# Microcontroller.net
KiCad netlist of a schematic drawn in Altium Designer
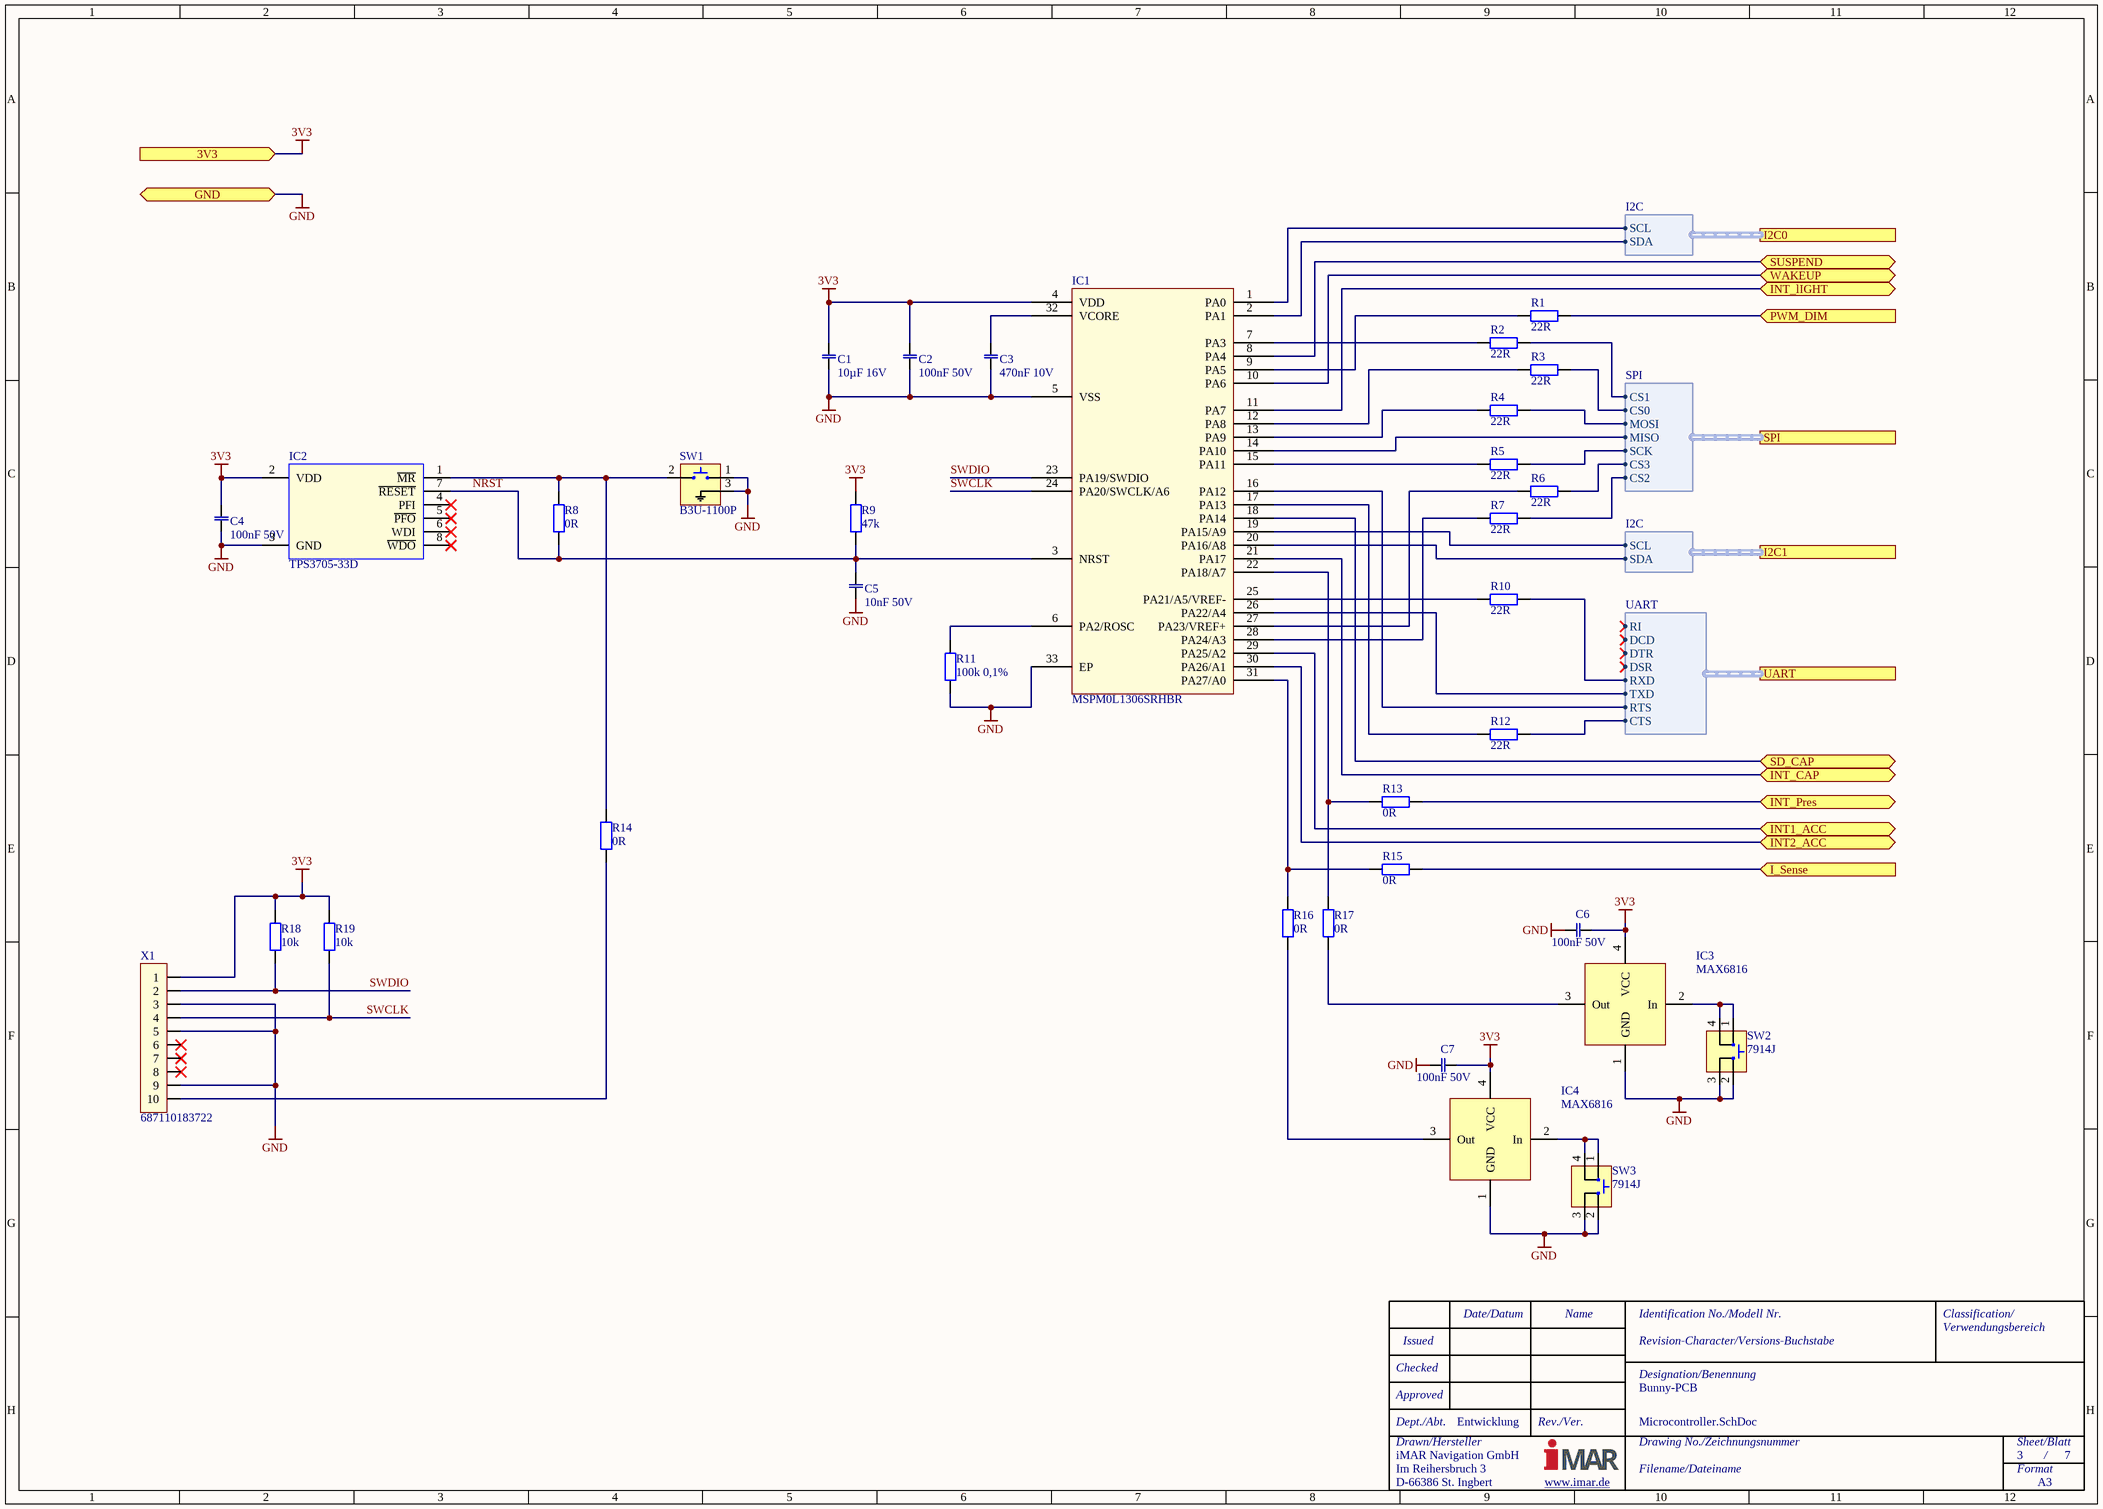
[diagram p0: Microcontroller.SchDoc]

(export (version "E")
  (design (tool "Eeschema 10.0.6"))
  (components
    (comp (ref "C1")
      (value "10µF 16V")
      (footprint "CAPC1608L")
      (description "10µF  16V  Ceramic  0603  10%  X5R")
      (fields (field (name "TOLERANCE") "10%") (field (name "MANUFACTURER") "unspecified"))
      (libsource (lib "iMAR Workspace") (part "Kondensator"))
    )
    (comp (ref "C2")
      (value "100nF 50V")
      (footprint "CAPC1005N")
      (description "100nF  50V  Ceramic  0402  10%  X7R")
      (fields (field (name "VOLTAGE") "50V") (field (name "MANUFACTURER") "unspecified"))
      (libsource (lib "iMAR Workspace") (part "Kondensator"))
    )
    (comp (ref "C3")
      (value "470nF 10V")
      (footprint "CAPC1005N")
      (description "470nF  10V  Ceramic  0402  10%  X5R")
      (fields (field (name "MANUFACTURER") "unspecified") (field (name "VOLTAGE") "10V"))
      (libsource (lib "iMAR Workspace") (part "Kondensator"))
    )
    (comp (ref "C4")
      (value "100nF 50V")
      (footprint "CAPC1005N")
      (description "100nF  50V  Ceramic  0402  10%  X7R")
      (fields (field (name "VOLTAGE") "50V") (field (name "MANUFACTURER") "unspecified"))
      (libsource (lib "iMAR Workspace") (part "Kondensator"))
    )
    (comp (ref "C5")
      (value "10nF 50V")
      (footprint "CAPC1005N")
      (description "10nF  50V  Ceramic  0402  10%  X7R")
      (fields (field (name "MANUFACTURER") "unspecified") (field (name "VOLTAGE") "50V"))
      (libsource (lib "iMAR Workspace") (part "Kondensator"))
    )
    (comp (ref "C6")
      (value "100nF 50V")
      (footprint "CAPC1005N")
      (description "100nF  50V  Ceramic  0402  10%  X7R")
      (fields (field (name "VOLTAGE") "50V") (field (name "MANUFACTURER") "unspecified"))
      (libsource (lib "iMAR Workspace") (part "Kondensator"))
    )
    (comp (ref "C7")
      (value "100nF 50V")
      (footprint "CAPC1005N")
      (description "100nF  50V  Ceramic  0402  10%  X7R")
      (fields (field (name "VOLTAGE") "50V") (field (name "MANUFACTURER") "unspecified"))
      (libsource (lib "iMAR Workspace") (part "Kondensator"))
    )
    (comp (ref "IC1")
      (value "MSPM0L1306SRHBR")
      (footprint "QFN50P500X500X80_HS-33N")
      (description "ARM Microcontrollers - MCU 32-MHz Arm Cortex - M0+ MCU with 64-KB")
      (fields (field (name "MANUFACTURER") "TEXAS INSTRUMENTS"))
      (libsource (lib "iMAR Workspace") (part "MSPM0L1306RHB"))
    )
    (comp (ref "IC2")
      (value "TPS3705-33D")
      (footprint "SOIC127P600X175-8N")
      (description "Überwachungsschaltung, Active-Low, Push-Pull-Reset, 2 Überwachungsschaltungen, 2V-6Vin, SOIC-8")
      (fields (field (name "MANUFACTURER") "TEXAS INSTRUMENTS"))
      (libsource (lib "iMAR Workspace") (part "TPS3705-33D"))
    )
    (comp (ref "IC3")
      (value "MAX6816")
      (footprint "SOT190P237X120-4N")
      (description "CMOS Switch Debouncers ±15kV ESD-Protected, Single/Dual/Octal,")
      (fields (field (name "MANUFACTURER") "MAXIM INTEGRATED"))
      (libsource (lib "iMAR Workspace") (part "MAX6816"))
    )
    (comp (ref "IC4")
      (value "MAX6816")
      (footprint "SOT190P237X120-4N")
      (description "CMOS Switch Debouncers ±15kV ESD-Protected, Single/Dual/Octal,")
      (fields (field (name "MANUFACTURER") "MAXIM INTEGRATED"))
      (libsource (lib "iMAR Workspace") (part "MAX6816"))
    )
    (comp (ref "R1")
      (value "22R")
      (footprint "RESC1005L")
      (description "22R  0402  62mW  1%  100ppm  50V")
      (fields (field (name "MANUFACTURER") "unspecified") (field (name "POWER") "62mW"))
      (libsource (lib "") (part "Widerstand_1"))
    )
    (comp (ref "R2")
      (value "22R")
      (footprint "RESC1005L")
      (description "22R  0402  62mW  1%  100ppm  50V")
      (fields (field (name "MANUFACTURER") "unspecified") (field (name "POWER") "62mW"))
      (libsource (lib "") (part "Widerstand_1"))
    )
    (comp (ref "R3")
      (value "22R")
      (footprint "RESC1005L")
      (description "22R  0402  62mW  1%  100ppm  50V")
      (fields (field (name "MANUFACTURER") "unspecified") (field (name "POWER") "62mW"))
      (libsource (lib "") (part "Widerstand_1"))
    )
    (comp (ref "R4")
      (value "22R")
      (footprint "RESC1005L")
      (description "22R  0402  62mW  1%  100ppm  50V")
      (fields (field (name "MANUFACTURER") "unspecified") (field (name "POWER") "62mW"))
      (libsource (lib "") (part "Widerstand_1"))
    )
    (comp (ref "R5")
      (value "22R")
      (footprint "RESC1005L")
      (description "22R  0402  62mW  1%  100ppm  50V")
      (fields (field (name "MANUFACTURER") "unspecified") (field (name "POWER") "62mW"))
      (libsource (lib "") (part "Widerstand_1"))
    )
    (comp (ref "R6")
      (value "22R")
      (footprint "RESC1005L")
      (description "22R  0402  62mW  1%  100ppm  50V")
      (fields (field (name "MANUFACTURER") "unspecified") (field (name "POWER") "62mW"))
      (libsource (lib "") (part "Widerstand_1"))
    )
    (comp (ref "R7")
      (value "22R")
      (footprint "RESC1005L")
      (description "22R  0402  62mW  1%  100ppm  50V")
      (fields (field (name "MANUFACTURER") "unspecified") (field (name "POWER") "62mW"))
      (libsource (lib "") (part "Widerstand_1"))
    )
    (comp (ref "R8")
      (value "0R")
      (footprint "RESC1005L")
      (description "0R  0402  0mW  0%  0ppm  0V")
      (fields (field (name "VOLTAGE") "0V") (field (name "TOLERANCE") "0%"))
      (libsource (lib "iMAR Workspace") (part "Widerstand"))
    )
    (comp (ref "R9")
      (value "47k")
      (footprint "RESC1005L")
      (description "47k  0402  62mW  1%  100ppm  50V")
      (fields (field (name "MANUFACTURER") "unspecified") (field (name "POWER") "62mW"))
      (libsource (lib "iMAR Workspace") (part "Widerstand"))
    )
    (comp (ref "R10")
      (value "22R")
      (footprint "RESC1005L")
      (description "22R  0402  62mW  1%  100ppm  50V")
      (fields (field (name "MANUFACTURER") "unspecified") (field (name "POWER") "62mW"))
      (libsource (lib "") (part "Widerstand_1"))
    )
    (comp (ref "R11")
      (value "100k 0,1%")
      (footprint "RESC1005L")
      (description "100k  0402  62mW  0,1%  25ppm  50V")
      (fields (field (name "POWER") "62mW") (field (name "VOLTAGE") "50V"))
      (libsource (lib "iMAR Workspace") (part "Widerstand"))
    )
    (comp (ref "R12")
      (value "22R")
      (footprint "RESC1005L")
      (description "22R  0402  62mW  1%  100ppm  50V")
      (fields (field (name "MANUFACTURER") "unspecified") (field (name "POWER") "62mW"))
      (libsource (lib "") (part "Widerstand_1"))
    )
    (comp (ref "R13")
      (value "0R")
      (footprint "RESC1005L")
      (description "0R  0402  0mW  0%  0ppm  0V")
      (fields (field (name "VOLTAGE") "0V") (field (name "TOLERANCE") "0%"))
      (libsource (lib "") (part "Widerstand_2"))
    )
    (comp (ref "R14")
      (value "0R")
      (footprint "RESC1005L")
      (description "0R  0402  0mW  0%  0ppm  0V")
      (fields (field (name "VOLTAGE") "0V") (field (name "TOLERANCE") "0%"))
      (libsource (lib "iMAR Workspace") (part "Widerstand"))
    )
    (comp (ref "R15")
      (value "0R")
      (footprint "RESC1005L")
      (description "0R  0402  0mW  0%  0ppm  0V")
      (fields (field (name "VOLTAGE") "0V") (field (name "TOLERANCE") "0%"))
      (libsource (lib "") (part "Widerstand_2"))
    )
    (comp (ref "R16")
      (value "0R")
      (footprint "RESC1005L")
      (description "0R  0402  0mW  0%  0ppm  0V")
      (fields (field (name "VOLTAGE") "0V") (field (name "TOLERANCE") "0%"))
      (libsource (lib "iMAR Workspace") (part "Widerstand"))
    )
    (comp (ref "R17")
      (value "0R")
      (footprint "RESC1005L")
      (description "0R  0402  0mW  0%  0ppm  0V")
      (fields (field (name "VOLTAGE") "0V") (field (name "TOLERANCE") "0%"))
      (libsource (lib "iMAR Workspace") (part "Widerstand"))
    )
    (comp (ref "R18")
      (value "10k")
      (footprint "RESC1005L")
      (description "10k  0402  62mW  1%  100ppm  50V")
      (fields (field (name "MANUFACTURER") "unspecified") (field (name "POWER") "62mW"))
      (libsource (lib "iMAR Workspace") (part "Widerstand"))
    )
    (comp (ref "R19")
      (value "10k")
      (footprint "RESC1005L")
      (description "10k  0402  62mW  1%  100ppm  50V")
      (fields (field (name "MANUFACTURER") "unspecified") (field (name "POWER") "62mW"))
      (libsource (lib "iMAR Workspace") (part "Widerstand"))
    )
    (comp (ref "SW1")
      (value "B3U-1100P")
      (footprint "OMRON_B3U-1100P")
      (fields (field (name "MANUFACTURER") "OMRON"))
      (libsource (lib "iMAR Workspace") (part "Taster SPST NO-Schliesser 2 Pin mit Gehäuse-Pin"))
    )
    (comp (ref "SW2")
      (value "7914J")
      (footprint "BOURNS_7914J")
      (description "SMD Pushbutton Sealed")
      (fields (field (name "MANUFACTURER") "BOURNS"))
      (libsource (lib "iMAR Workspace") (part "Taster SPST NO-Schliesser 4 Pins"))
    )
    (comp (ref "SW3")
      (value "7914J")
      (footprint "BOURNS_7914J")
      (description "SMD Pushbutton Sealed")
      (fields (field (name "MANUFACTURER") "BOURNS"))
      (libsource (lib "iMAR Workspace") (part "Taster SPST NO-Schliesser 4 Pins"))
    )
    (comp (ref "X1")
      (value "687110183722")
      (footprint "WE_687110183722")
      (description "WR-FPC 0.50 mm SMT ZIF Horizontal Bottom Contact")
      (fields (field (name "MANUFACTURER") "WUERTH ELEKTRONIK"))
      (libsource (lib "iMAR Workspace") (part "CON10"))
    )
  )
  (nets
    (net (code "4") (name "/CS0") (class "Default")
      (node (ref "R3") (pin "2") (pinfunction "2_2") (pintype "passive"))
    )
    (net (code "5") (name "/CS1") (class "Default")
      (node (ref "R2") (pin "2") (pinfunction "2_2") (pintype "passive"))
    )
    (net (code "6") (name "/CS2") (class "Default")
      (node (ref "R7") (pin "2") (pinfunction "2_2") (pintype "passive"))
    )
    (net (code "7") (name "/CS3") (class "Default")
      (node (ref "R6") (pin "2") (pinfunction "2_2") (pintype "passive"))
    )
    (net (code "8") (name "/CTS") (class "Default")
      (node (ref "R12") (pin "2") (pinfunction "2_2") (pintype "passive"))
    )
    (net (code "9") (name "/INT1_ACC") (class "Default")
      (node (ref "IC1") (pin "29") (pinfunction "PA25/A2_29") (pintype "passive"))
    )
    (net (code "10") (name "/INT2_ACC") (class "Default")
      (node (ref "IC1") (pin "30") (pinfunction "PA26/A1_30") (pintype "passive"))
    )
    (net (code "11") (name "/INT_CAP") (class "Default")
      (node (ref "IC1") (pin "21") (pinfunction "PA17_21") (pintype "passive"))
    )
    (net (code "12") (name "/INT_Pres") (class "Default")
      (node (ref "R13") (pin "1") (pinfunction "1_1") (pintype "passive"))
    )
    (net (code "13") (name "/INT_lIGHT") (class "Default")
      (node (ref "IC1") (pin "11") (pinfunction "PA7_11") (pintype "passive"))
    )
    (net (code "14") (name "/I_Sense") (class "Default")
      (node (ref "R15") (pin "1") (pinfunction "1_1") (pintype "passive"))
    )
    (net (code "15") (name "/MISO") (class "Default")
      (node (ref "IC1") (pin "14") (pinfunction "PA10_14") (pintype "passive"))
    )
    (net (code "16") (name "/MOSI") (class "Default")
      (node (ref "R4") (pin "2") (pinfunction "2_2") (pintype "passive"))
    )
    (net (code "17") (name "/NRST") (class "Default")
      (node (ref "C5") (pin "2") (pinfunction "2_2") (pintype "passive"))
      (node (ref "IC1") (pin "3") (pinfunction "NRST_3") (pintype "passive"))
      (node (ref "IC2") (pin "7") (pinfunction "~{RESET}_7") (pintype "passive"))
      (node (ref "R8") (pin "1") (pinfunction "1_1") (pintype "passive"))
      (node (ref "R9") (pin "1") (pinfunction "1_1") (pintype "passive"))
    )
    (net (code "18") (name "/PWM_DIM") (class "Default")
      (node (ref "R1") (pin "2") (pinfunction "2_2") (pintype "passive"))
    )
    (net (code "19") (name "/RTS") (class "Default")
      (node (ref "IC1") (pin "16") (pinfunction "PA12_16") (pintype "passive"))
    )
    (net (code "20") (name "/RXD") (class "Default")
      (node (ref "R10") (pin "2") (pinfunction "2_2") (pintype "passive"))
    )
    (net (code "21") (name "/SCK") (class "Default")
      (node (ref "R5") (pin "2") (pinfunction "2_2") (pintype "passive"))
    )
    (net (code "22") (name "/SD_CAP") (class "Default")
      (node (ref "IC1") (pin "18") (pinfunction "PA14_18") (pintype "passive"))
    )
    (net (code "23") (name "/SUSPEND") (class "Default")
      (node (ref "IC1") (pin "8") (pinfunction "PA4_8") (pintype "passive"))
    )
    (net (code "24") (name "/SWCLK") (class "Default")
      (node (ref "IC1") (pin "24") (pinfunction "PA20/SWCLK/A6_24") (pintype "passive"))
      (node (ref "R19") (pin "1") (pinfunction "1_1") (pintype "passive"))
      (node (ref "X1") (pin "4") (pinfunction "4_4") (pintype "passive"))
    )
    (net (code "25") (name "/SWDIO") (class "Default")
      (node (ref "IC1") (pin "23") (pinfunction "PA19/SWDIO_23") (pintype "passive"))
      (node (ref "R18") (pin "1") (pinfunction "1_1") (pintype "passive"))
      (node (ref "X1") (pin "2") (pinfunction "2_2") (pintype "passive"))
    )
    (net (code "26") (name "/TXD") (class "Default")
      (node (ref "IC1") (pin "26") (pinfunction "PA22/A4_26") (pintype "passive"))
    )
    (net (code "27") (name "/WAKEUP") (class "Default")
      (node (ref "IC1") (pin "10") (pinfunction "PA6_10") (pintype "passive"))
    )
    (net (code "31") (name "3V3") (class "Default")
      (node (ref "C1") (pin "2") (pinfunction "2_2") (pintype "passive"))
      (node (ref "C2") (pin "2") (pinfunction "2_2") (pintype "passive"))
      (node (ref "C4") (pin "2") (pinfunction "2_2") (pintype "passive"))
      (node (ref "C6") (pin "2") (pinfunction "2_2") (pintype "passive"))
      (node (ref "C7") (pin "2") (pinfunction "2_2") (pintype "passive"))
      (node (ref "IC1") (pin "4") (pinfunction "VDD_4") (pintype "passive"))
      (node (ref "IC2") (pin "2") (pinfunction "VDD_2") (pintype "passive"))
      (node (ref "IC3") (pin "4") (pinfunction "VCC_4") (pintype "passive"))
      (node (ref "IC4") (pin "4") (pinfunction "VCC_4") (pintype "passive"))
      (node (ref "R18") (pin "2") (pinfunction "2_2") (pintype "passive"))
      (node (ref "R19") (pin "2") (pinfunction "2_2") (pintype "passive"))
      (node (ref "R9") (pin "2") (pinfunction "2_2") (pintype "passive"))
      (node (ref "X1") (pin "1") (pinfunction "1_1") (pintype "passive"))
    )
    (net (code "32") (name "GND") (class "Default")
      (node (ref "C1") (pin "1") (pinfunction "1_1") (pintype "passive"))
      (node (ref "C2") (pin "1") (pinfunction "1_1") (pintype "passive"))
      (node (ref "C3") (pin "1") (pinfunction "1_1") (pintype "passive"))
      (node (ref "C4") (pin "1") (pinfunction "1_1") (pintype "passive"))
      (node (ref "C5") (pin "1") (pinfunction "1_1") (pintype "passive"))
      (node (ref "C6") (pin "1") (pinfunction "1_1") (pintype "passive"))
      (node (ref "C7") (pin "1") (pinfunction "1_1") (pintype "passive"))
      (node (ref "IC1") (pin "33") (pinfunction "EP_33") (pintype "passive"))
      (node (ref "IC1") (pin "5") (pinfunction "VSS_5") (pintype "passive"))
      (node (ref "IC2") (pin "3") (pinfunction "GND_3") (pintype "passive"))
      (node (ref "IC3") (pin "1") (pinfunction "GND_1") (pintype "passive"))
      (node (ref "IC4") (pin "1") (pinfunction "GND_1") (pintype "passive"))
      (node (ref "R11") (pin "1") (pinfunction "1_1") (pintype "passive"))
      (node (ref "SW1") (pin "1") (pinfunction "1_1") (pintype "passive"))
      (node (ref "SW1") (pin "3") (pinfunction "3_3") (pintype "passive"))
      (node (ref "SW2") (pin "2") (pinfunction "2_2") (pintype "passive"))
      (node (ref "SW2") (pin "3") (pinfunction "3_3") (pintype "passive"))
      (node (ref "SW3") (pin "2") (pinfunction "2_2") (pintype "passive"))
      (node (ref "SW3") (pin "3") (pinfunction "3_3") (pintype "passive"))
      (node (ref "X1") (pin "3") (pinfunction "3_3") (pintype "passive"))
      (node (ref "X1") (pin "5") (pinfunction "5_5") (pintype "passive"))
      (node (ref "X1") (pin "9") (pinfunction "9_9") (pintype "passive"))
    )
    (net (code "33") (name "Net-(IC1A-PA2{slash}ROSC)") (class "Default")
      (node (ref "IC1") (pin "6") (pinfunction "PA2/ROSC_6") (pintype "passive"))
      (node (ref "R11") (pin "2") (pinfunction "2_2") (pintype "passive"))
    )
    (net (code "34") (name "Net-(IC1A-PA3)") (class "Default")
      (node (ref "IC1") (pin "7") (pinfunction "PA3_7") (pintype "passive"))
      (node (ref "R2") (pin "1") (pinfunction "1_1") (pintype "passive"))
    )
    (net (code "35") (name "Net-(IC1A-PA5)") (class "Default")
      (node (ref "IC1") (pin "9") (pinfunction "PA5_9") (pintype "passive"))
      (node (ref "R1") (pin "1") (pinfunction "1_1") (pintype "passive"))
    )
    (net (code "36") (name "Net-(IC1A-PA8)") (class "Default")
      (node (ref "IC1") (pin "12") (pinfunction "PA8_12") (pintype "passive"))
      (node (ref "R3") (pin "1") (pinfunction "1_1") (pintype "passive"))
    )
    (net (code "37") (name "Net-(IC1A-PA9)") (class "Default")
      (node (ref "IC1") (pin "13") (pinfunction "PA9_13") (pintype "passive"))
      (node (ref "R4") (pin "1") (pinfunction "1_1") (pintype "passive"))
    )
    (net (code "38") (name "Net-(IC1A-PA11)") (class "Default")
      (node (ref "IC1") (pin "15") (pinfunction "PA11_15") (pintype "passive"))
      (node (ref "R5") (pin "1") (pinfunction "1_1") (pintype "passive"))
    )
    (net (code "39") (name "Net-(IC1A-PA13)") (class "Default")
      (node (ref "IC1") (pin "17") (pinfunction "PA13_17") (pintype "passive"))
      (node (ref "R12") (pin "1") (pinfunction "1_1") (pintype "passive"))
    )
    (net (code "40") (name "Net-(IC1A-PA18{slash}A7)") (class "Default")
      (node (ref "IC1") (pin "22") (pinfunction "PA18/A7_22") (pintype "passive"))
      (node (ref "R13") (pin "2") (pinfunction "2_2") (pintype "passive"))
      (node (ref "R17") (pin "2") (pinfunction "2_2") (pintype "passive"))
    )
    (net (code "41") (name "Net-(IC1A-PA21{slash}A5{slash}VREF-)") (class "Default")
      (node (ref "IC1") (pin "25") (pinfunction "PA21/A5/VREF-_25") (pintype "passive"))
      (node (ref "R10") (pin "1") (pinfunction "1_1") (pintype "passive"))
    )
    (net (code "42") (name "Net-(IC1A-PA23{slash}VREF+)") (class "Default")
      (node (ref "IC1") (pin "27") (pinfunction "PA23/VREF+_27") (pintype "passive"))
      (node (ref "R6") (pin "1") (pinfunction "1_1") (pintype "passive"))
    )
    (net (code "43") (name "Net-(IC1A-PA24{slash}A3)") (class "Default")
      (node (ref "IC1") (pin "28") (pinfunction "PA24/A3_28") (pintype "passive"))
      (node (ref "R7") (pin "1") (pinfunction "1_1") (pintype "passive"))
    )
    (net (code "44") (name "Net-(IC1A-PA27{slash}A0)") (class "Default")
      (node (ref "IC1") (pin "31") (pinfunction "PA27/A0_31") (pintype "passive"))
      (node (ref "R15") (pin "2") (pinfunction "2_2") (pintype "passive"))
      (node (ref "R16") (pin "2") (pinfunction "2_2") (pintype "passive"))
    )
    (net (code "45") (name "Net-(IC1A-VCORE)") (class "Default")
      (node (ref "C3") (pin "2") (pinfunction "2_2") (pintype "passive"))
      (node (ref "IC1") (pin "32") (pinfunction "VCORE_32") (pintype "passive"))
    )
    (net (code "46") (name "Net-(IC2-~{MR})") (class "Default")
      (node (ref "IC2") (pin "1") (pinfunction "~{MR}_1") (pintype "passive"))
      (node (ref "R14") (pin "2") (pinfunction "2_2") (pintype "passive"))
      (node (ref "R8") (pin "2") (pinfunction "2_2") (pintype "passive"))
      (node (ref "SW1") (pin "2") (pinfunction "2_2") (pintype "passive"))
    )
    (net (code "47") (name "Net-(IC3-In)") (class "Default")
      (node (ref "IC3") (pin "2") (pinfunction "In_2") (pintype "passive"))
      (node (ref "SW2") (pin "1") (pinfunction "1_1") (pintype "passive"))
      (node (ref "SW2") (pin "4") (pinfunction "4_4") (pintype "passive"))
    )
    (net (code "48") (name "Net-(IC3-Out)") (class "Default")
      (node (ref "IC3") (pin "3") (pinfunction "Out_3") (pintype "passive"))
      (node (ref "R17") (pin "1") (pinfunction "1_1") (pintype "passive"))
    )
    (net (code "49") (name "Net-(IC4-In)") (class "Default")
      (node (ref "IC4") (pin "2") (pinfunction "In_2") (pintype "passive"))
      (node (ref "SW3") (pin "1") (pinfunction "1_1") (pintype "passive"))
      (node (ref "SW3") (pin "4") (pinfunction "4_4") (pintype "passive"))
    )
    (net (code "50") (name "Net-(IC4-Out)") (class "Default")
      (node (ref "IC4") (pin "3") (pinfunction "Out_3") (pintype "passive"))
      (node (ref "R16") (pin "1") (pinfunction "1_1") (pintype "passive"))
    )
    (net (code "51") (name "Net-(R14-Pad1)") (class "Default")
      (node (ref "R14") (pin "1") (pinfunction "1_1") (pintype "passive"))
      (node (ref "X1") (pin "10") (pinfunction "10_10") (pintype "passive"))
    )
    (net (code "52") (name "unconnected-(IC1A-PA0-Pad1)") (class "Default")
      (node (ref "IC1") (pin "1") (pinfunction "PA0_1") (pintype "passive"))
    )
    (net (code "53") (name "unconnected-(IC1A-PA1-Pad2)") (class "Default")
      (node (ref "IC1") (pin "2") (pinfunction "PA1_2") (pintype "passive"))
    )
    (net (code "54") (name "unconnected-(IC1A-PA15{slash}A9-Pad19)") (class "Default")
      (node (ref "IC1") (pin "19") (pinfunction "PA15/A9_19") (pintype "passive"))
    )
    (net (code "55") (name "unconnected-(IC1A-PA16{slash}A8-Pad20)") (class "Default")
      (node (ref "IC1") (pin "20") (pinfunction "PA16/A8_20") (pintype "passive"))
    )
    (net (code "56") (name "unconnected-(IC2-PFI-Pad4)") (class "Default")
      (node (ref "IC2") (pin "4") (pinfunction "PFI_4") (pintype "passive+no_connect"))
    )
    (net (code "57") (name "unconnected-(IC2-WDI-Pad6)") (class "Default")
      (node (ref "IC2") (pin "6") (pinfunction "WDI_6") (pintype "passive+no_connect"))
    )
    (net (code "58") (name "unconnected-(IC2-~{PFO}-Pad5)") (class "Default")
      (node (ref "IC2") (pin "5") (pinfunction "~{PFO}_5") (pintype "passive+no_connect"))
    )
    (net (code "59") (name "unconnected-(IC2-~{WDO}-Pad8)") (class "Default")
      (node (ref "IC2") (pin "8") (pinfunction "~{WDO}_8") (pintype "passive+no_connect"))
    )
    (net (code "60") (name "unconnected-(X1-Pad6)") (class "Default")
      (node (ref "X1") (pin "6") (pinfunction "6_6") (pintype "passive+no_connect"))
    )
    (net (code "61") (name "unconnected-(X1-Pad7)") (class "Default")
      (node (ref "X1") (pin "7") (pinfunction "7_7") (pintype "passive+no_connect"))
    )
    (net (code "62") (name "unconnected-(X1-Pad8)") (class "Default")
      (node (ref "X1") (pin "8") (pinfunction "8_8") (pintype "passive+no_connect"))
    )
  )
)
